# AquaEye_2025-10-07.net
KiCad netlist of a schematic drawn in EasyEDA Pro
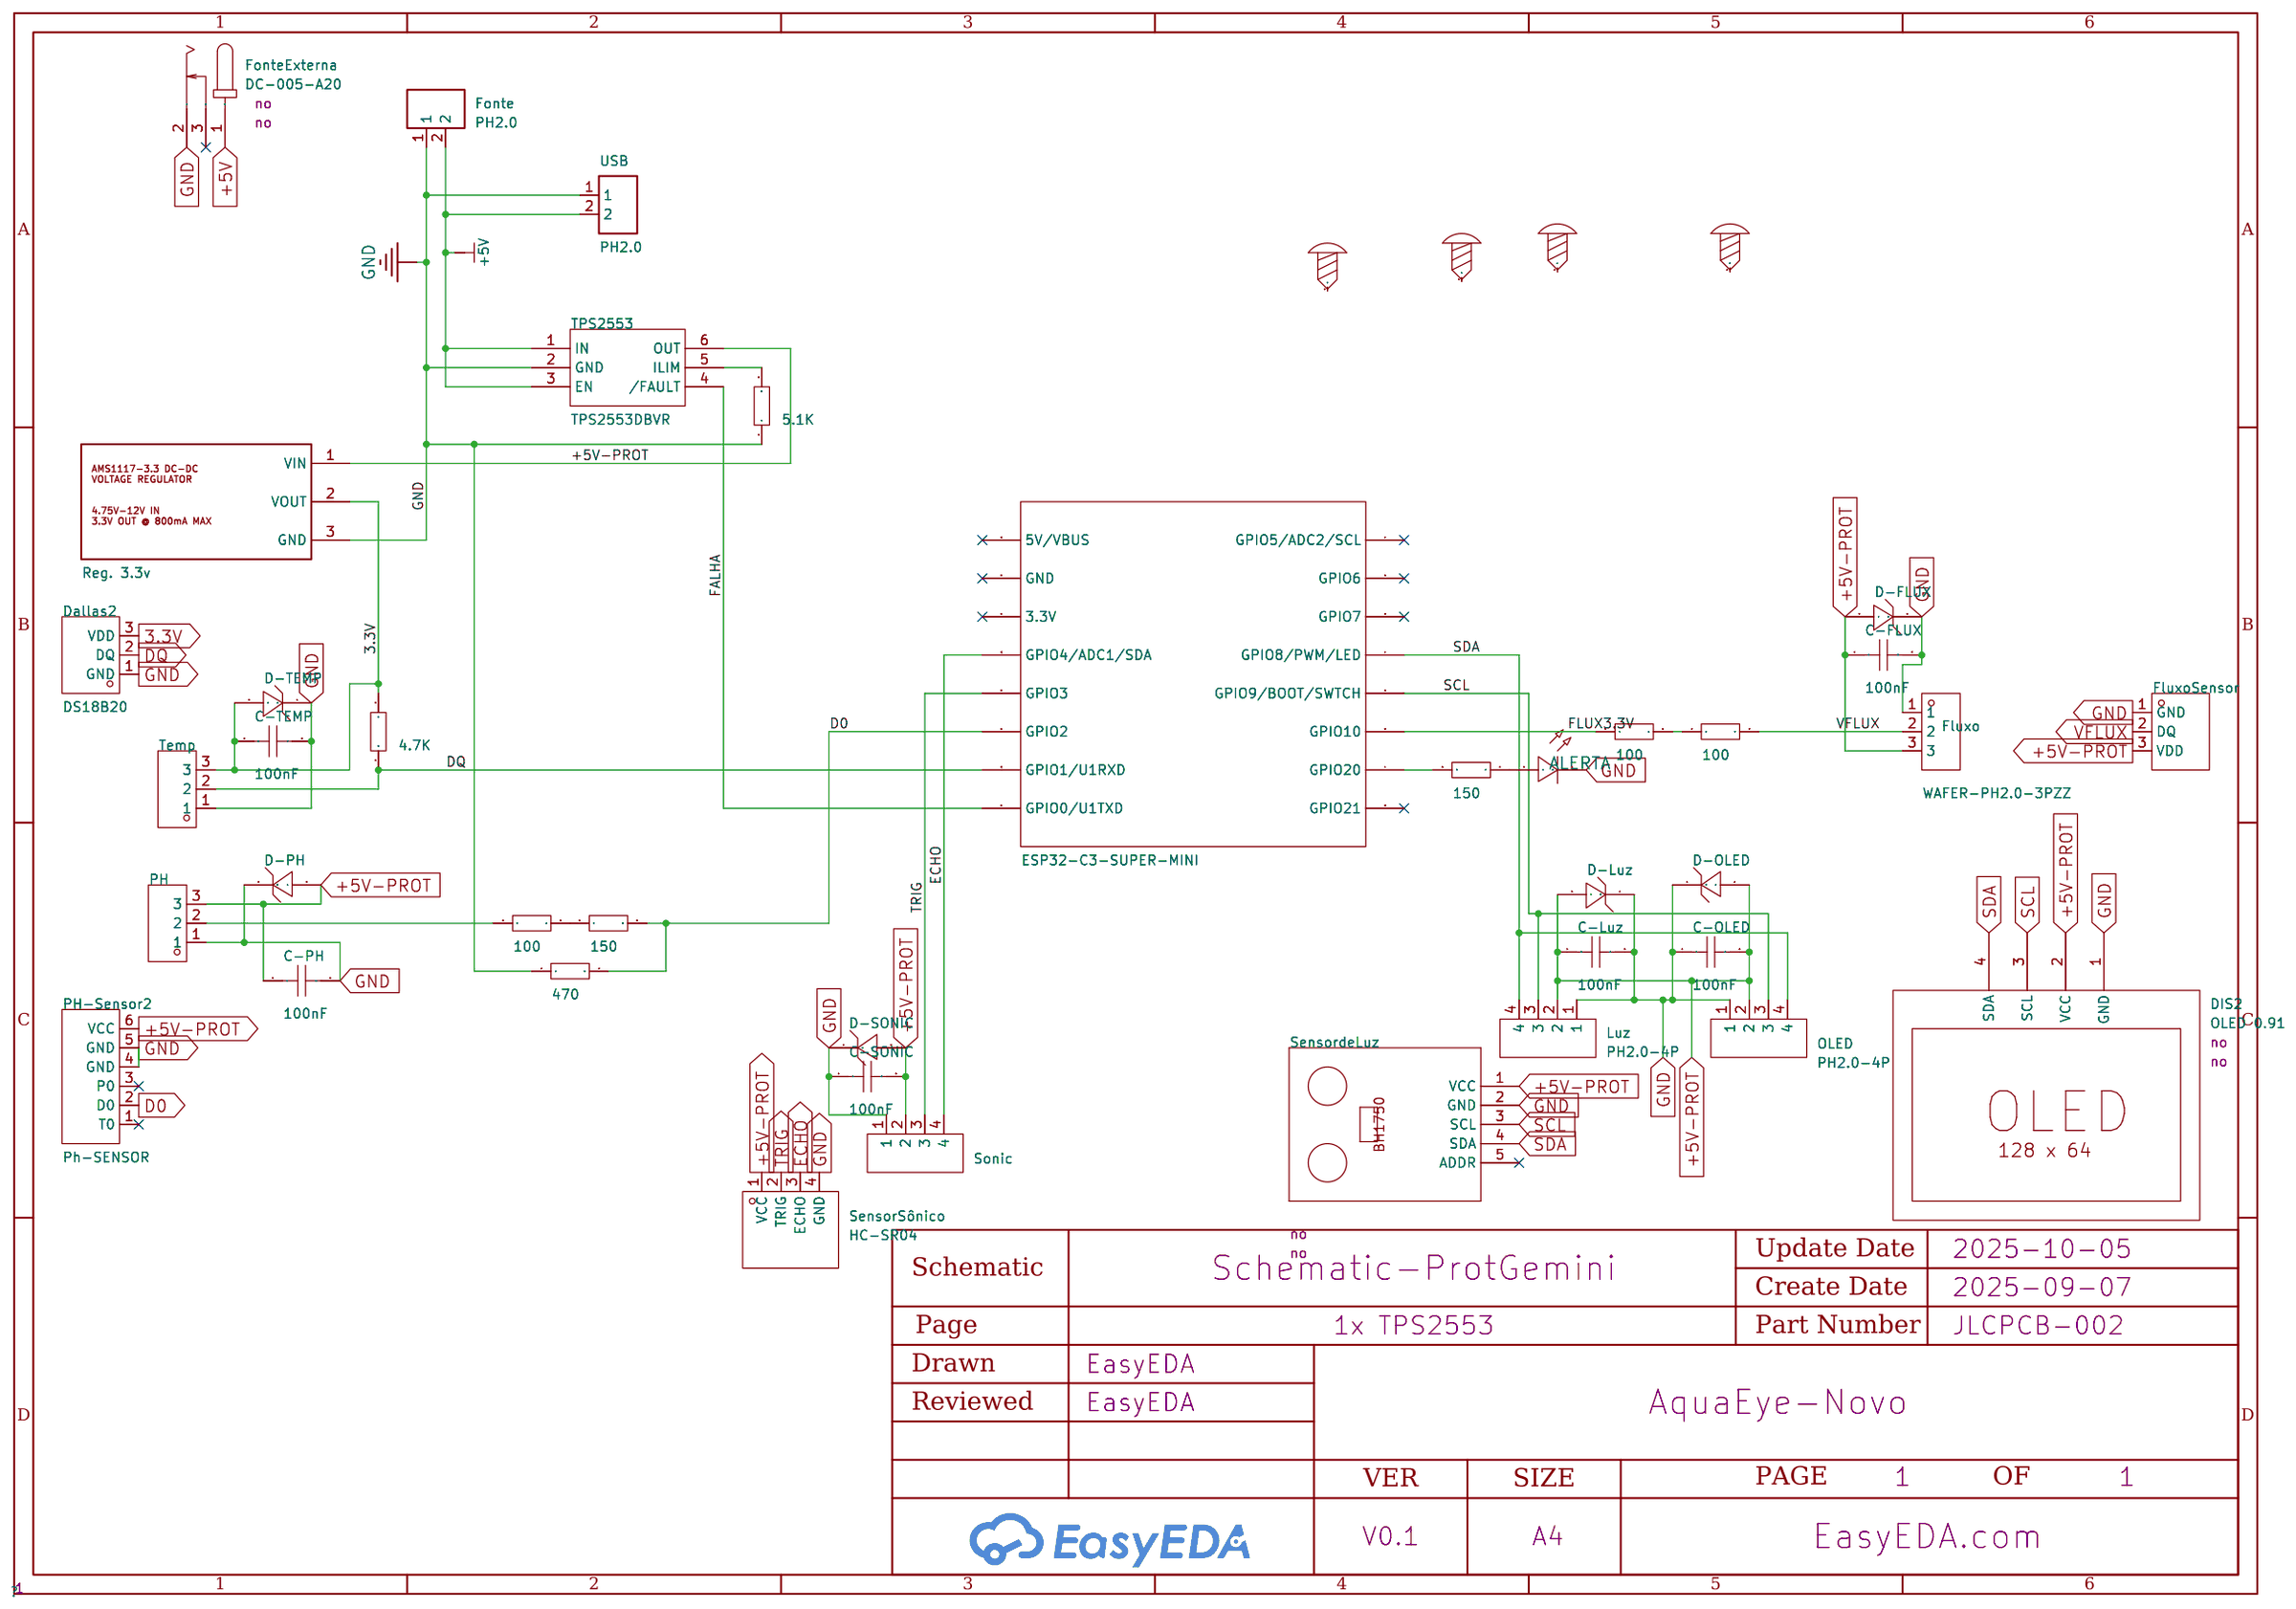
[diagram p0: schematic sheet]

(export (version "E")
  (design (tool "Eeschema 10.0.6"))
  (components
    (comp (ref "ALERTA")
      (value "~")
      (footprint "easyedapro:LED0805-R-RD")
      (libsource (lib "easyedapro") (part "LED_R"))
    )
    (comp (ref "C-FLUX")
      (value "100nF")
      (footprint "easyedapro:CAP-TH_L6.5-W4.0-P5.00-D0.6-S1.20")
      (fields
        (field (name "Manufacturer Part") "DCS104Z26Y5VF6FJ5A0")
        (field (name "Manufacturer") "SHM(南方宏明)")
      )
      (libsource (lib "easyedapro") (part "DCS104Z26Y5VF6FJ5A0"))
    )
    (comp (ref "C-Luz")
      (value "100nF")
      (footprint "easyedapro:CAP-TH_L6.5-W4.0-P5.00-D0.6-S1.20")
      (fields
        (field (name "Manufacturer Part") "DCS104Z26Y5VF6FJ5A0")
        (field (name "Manufacturer") "SHM(南方宏明)")
      )
      (libsource (lib "easyedapro") (part "DCS104Z26Y5VF6FJ5A0"))
    )
    (comp (ref "C-OLED")
      (value "100nF")
      (footprint "easyedapro:CAP-TH_L6.5-W4.0-P5.00-D0.6-S1.20")
      (fields
        (field (name "Manufacturer Part") "DCS104Z26Y5VF6FJ5A0")
        (field (name "Manufacturer") "SHM(南方宏明)")
      )
      (libsource (lib "easyedapro") (part "DCS104Z26Y5VF6FJ5A0"))
    )
    (comp (ref "C-PH")
      (value "100nF")
      (footprint "easyedapro:CAP-TH_L6.5-W4.0-P5.00-D0.6-S1.20")
      (fields
        (field (name "Manufacturer Part") "DCS104Z26Y5VF6FJ5A0")
        (field (name "Manufacturer") "SHM(南方宏明)")
      )
      (libsource (lib "easyedapro") (part "DCS104Z26Y5VF6FJ5A0"))
    )
    (comp (ref "C-SONIC")
      (value "100nF")
      (footprint "easyedapro:CAP-TH_L6.5-W4.0-P5.00-D0.6-S1.20")
      (fields
        (field (name "Manufacturer Part") "DCS104Z26Y5VF6FJ5A0")
        (field (name "Manufacturer") "SHM(南方宏明)")
      )
      (libsource (lib "easyedapro") (part "DCS104Z26Y5VF6FJ5A0"))
    )
    (comp (ref "C-TEMP")
      (value "100nF")
      (footprint "easyedapro:CAP-TH_L6.5-W4.0-P5.00-D0.6-S1.20")
      (fields
        (field (name "Manufacturer Part") "DCS104Z26Y5VF6FJ5A0")
        (field (name "Manufacturer") "SHM(南方宏明)")
      )
      (libsource (lib "easyedapro") (part "DCS104Z26Y5VF6FJ5A0"))
    )
    (comp (ref "D-FLUX")
      (value "SMAJ5.0A")
      (footprint "easyedapro:SMA_L4.3-W2.6-LS5.2-RD")
      (libsource (lib "easyedapro") (part "SMAJ5.0A-C132575"))
    )
    (comp (ref "D-Luz")
      (value "SMAJ5.0A")
      (footprint "easyedapro:SMA_L4.3-W2.6-LS5.2-RD")
      (libsource (lib "easyedapro") (part "SMAJ5.0A-C132575"))
    )
    (comp (ref "D-OLED")
      (value "SMAJ5.0A")
      (footprint "easyedapro:SMA_L4.3-W2.6-LS5.2-RD")
      (libsource (lib "easyedapro") (part "SMAJ5.0A-C132575"))
    )
    (comp (ref "D-PH")
      (value "SMAJ5.0A")
      (footprint "easyedapro:SMA_L4.3-W2.6-LS5.2-RD")
      (libsource (lib "easyedapro") (part "SMAJ5.0A-C132575"))
    )
    (comp (ref "D-SONIC")
      (value "SMAJ5.0A")
      (footprint "easyedapro:SMA_L4.3-W2.6-LS5.2-RD")
      (libsource (lib "easyedapro") (part "SMAJ5.0A-C132575"))
    )
    (comp (ref "D-TEMP")
      (value "SMAJ5.0A")
      (footprint "easyedapro:SMA_L4.3-W2.6-LS5.2-RD")
      (libsource (lib "easyedapro") (part "SMAJ5.0A-C132575"))
    )
    (comp (ref "Dallas2")
      (value "DS18B20")
      (footprint "easyedapro:TO-92-SMD_L4.6-W4.6-P1.27_DS18B20")
      (fields (field (name "Manufacturer") "UMW(友台半导体)"))
      (libsource (lib "easyedapro") (part "DS18B20A10T6"))
    )
    (comp (ref "DIS2")
      (value "OLED 0.91")
      (fields
        (field (name "Manufacturer Part") "SSD1306 I2C OLED")
        (field (name "Add into BOM") "no")
        (field (name "Convert to PCB") "no")
      )
      (libsource (lib "easyedapro") (part "I2C OLED Module (128x64)"))
    )
    (comp (ref "Fluxo")
      (value "WAFER-PH2.0-3PZZ")
      (footprint "easyedapro:CONN-TH_PH2.0D-L-3P")
      (fields (field (name "Manufacturer") "XUNPU(讯普)"))
      (libsource (lib "easyedapro") (part "WAFER-PH2.0-3PZZ"))
    )
    (comp (ref "FluxoSensor")
      (value "DS18B20A10T6")
      (footprint "easyedapro:TO-92-SMD_L4.6-W4.6-P1.27_DS18B20")
      (fields (field (name "Manufacturer") "Mysentech(敏源传感)"))
      (libsource (lib "easyedapro") (part "DS18B20A10T6"))
    )
    (comp (ref "Fonte")
      (value "PH2.0")
      (footprint "easyedapro:CONN-TH_WAFER-PH2.0-2PZZ-Y62")
      (fields
        (field (name "Manufacturer Part") "WAFER-PH2.0-2PZZ-Y62")
        (field (name "Manufacturer") "XUNPU(讯普)")
      )
      (libsource (lib "easyedapro") (part "PH2.0"))
    )
    (comp (ref "FonteExterna")
      (value "DC-005-A20")
      (fields
        (field (name "Manufacturer") "Yuandi(元迪)")
        (field (name "Add into BOM") "no")
        (field (name "Convert to PCB") "no")
      )
      (libsource (lib "easyedapro") (part "DC-005"))
    )
    (comp (ref "Luz")
      (value "PH2.0-4P")
      (footprint "easyedapro:CONN-TH_PH2.0-4P")
      (fields (field (name "Manufacturer") "CAX(创都)"))
      (libsource (lib "easyedapro") (part "PH2.0-4P"))
    )
    (comp (ref "M1")
      (value "Reg. 3.3v")
      (libsource (lib "easyedapro") (part "AMS1117-3.3 DC-DC Voltage Regulator"))
    )
    (comp (ref "OLED")
      (value "PH2.0-4P")
      (footprint "easyedapro:CONN-TH_PH2.0-4P")
      (fields (field (name "Manufacturer") "CAX(创都)"))
      (libsource (lib "easyedapro") (part "PH2.0-4P"))
    )
    (comp (ref "PH")
      (value "WAFER-PH2.0-3PZZ")
      (footprint "easyedapro:CONN-TH_PH2.0D-L-3P")
      (fields (field (name "Manufacturer") "XUNPU(讯普)"))
      (libsource (lib "easyedapro") (part "WAFER-PH2.0-3PZZ"))
    )
    (comp (ref "PH-Sensor2") (value "Ph-SENSOR") (libsource (lib "easyedapro") (part "Ph-SENSOR")))
    (comp (ref "R5") (value "100") (footprint "easyedapro:R0603") (libsource (lib "easyedapro") (part "Res")))
    (comp (ref "R7") (value "100") (footprint "easyedapro:R0603") (libsource (lib "easyedapro") (part "Res")))
    (comp (ref "R8") (value "150") (footprint "easyedapro:R0603") (libsource (lib "easyedapro") (part "Res")))
    (comp (ref "R9") (value "470") (footprint "easyedapro:R0603") (libsource (lib "easyedapro") (part "Res")))
    (comp (ref "R10")
      (value "100")
      (footprint "easyedapro:R0603")
      (libsource (lib "easyedapro") (part "Res"))
    )
    (comp (ref "SCREW1")
      (value "~")
      (footprint "easyedapro:Screw-Hole-M2")
      (libsource (lib "easyedapro") (part "Screw-Hole"))
    )
    (comp (ref "SCREW2")
      (value "~")
      (footprint "easyedapro:Screw-Hole-M2")
      (libsource (lib "easyedapro") (part "Screw-Hole"))
    )
    (comp (ref "SCREW3")
      (value "~")
      (footprint "easyedapro:Screw-Hole-M2")
      (libsource (lib "easyedapro") (part "Screw-Hole"))
    )
    (comp (ref "SCREW4")
      (value "~")
      (footprint "easyedapro:Screw-Hole-M2")
      (libsource (lib "easyedapro") (part "Screw-Hole"))
    )
    (comp (ref "SensordeLuz")
      (value "~")
      (footprint "easyedapro:LIGHT-SENSOR-BH1750")
      (fields (field (name "Add into BOM") "no") (field (name "Convert to PCB") "no"))
      (libsource (lib "easyedapro") (part "LIGHT-SENSOR-BH1750_"))
    )
    (comp (ref "SensorSônico")
      (value "HC-SR04")
      (footprint "easyedapro:TH_HC-SR04V")
      (fields (field (name "Manufacturer") "Universal Microelectronics"))
      (libsource (lib "easyedapro") (part "HC-SR04"))
    )
    (comp (ref "Sonic")
      (value "PH2.0-4P")
      (footprint "easyedapro:CONN-TH_PH2.0-4P")
      (fields (field (name "Manufacturer") "CAX(创都)"))
      (libsource (lib "easyedapro") (part "PH2.0-4P"))
    )
    (comp (ref "Temp")
      (value "WAFER-PH2.0-3PZZ")
      (footprint "easyedapro:CONN-TH_PH2.0D-L-3P")
      (fields (field (name "Manufacturer") "XUNPU(讯普)"))
      (libsource (lib "easyedapro") (part "WAFER-PH2.0-3PZZ"))
    )
    (comp (ref "TPS2553")
      (value "TPS2553DBVR")
      (footprint "easyedapro:SOT-23-6_L2.9-W1.6-P0.95-LS2.8-BR")
      (fields (field (name "Manufacturer") "TI(德州仪器)"))
      (libsource (lib "easyedapro") (part "TPS2553DBVR"))
    )
    (comp (ref "U1")
      (value "4.7K")
      (footprint "easyedapro:R0603")
      (libsource (lib "easyedapro") (part "Res"))
    )
    (comp (ref "U2")
      (value "ESP32-C3-SUPER-MINI")
      (fields (field (name "Manufacturer") "Maker go"))
      (libsource (lib "easyedapro") (part "ESP32-C3-SUPER-MINI"))
    )
    (comp (ref "U3")
      (value "5.1K")
      (footprint "easyedapro:R0603")
      (libsource (lib "easyedapro") (part "Res"))
    )
    (comp (ref "U4") (value "150") (footprint "easyedapro:R0603") (libsource (lib "easyedapro") (part "Res")))
    (comp (ref "USB")
      (value "PH2.0")
      (footprint "easyedapro:CONN-TH_WAFER-PH2.0-2PZZ-Y62")
      (fields
        (field (name "Manufacturer Part") "WAFER-PH2.0-2PZZ-Y62")
        (field (name "Manufacturer") "XUNPU(讯普)")
      )
      (libsource (lib "easyedapro") (part "PH2.0"))
    )
  )
  (nets
    (net (code "1") (name "+5V") (class "Default")
      (node (ref "Fonte") (pin "2") (pinfunction "2_2") (pintype "unspecified"))
      (node (ref "FonteExterna") (pin "1") (pinfunction "1_1") (pintype "unspecified"))
      (node (ref "TPS2553") (pin "1") (pinfunction "IN_1") (pintype "unspecified"))
      (node (ref "TPS2553") (pin "3") (pinfunction "EN_3") (pintype "unspecified"))
      (node (ref "USB") (pin "2") (pinfunction "2_2") (pintype "unspecified"))
    )
    (net (code "2") (name "+5V-PROT") (class "Default")
      (node (ref "C-FLUX") (pin "1") (pinfunction "1_1") (pintype "unspecified"))
      (node (ref "C-Luz") (pin "1") (pinfunction "1_1") (pintype "unspecified"))
      (node (ref "C-OLED") (pin "2") (pinfunction "2_2") (pintype "unspecified"))
      (node (ref "C-PH") (pin "1") (pinfunction "1_1") (pintype "unspecified"))
      (node (ref "C-SONIC") (pin "2") (pinfunction "2_2") (pintype "unspecified"))
      (node (ref "D-FLUX") (pin "2") (pinfunction "A_2") (pintype "unspecified"))
      (node (ref "D-Luz") (pin "2") (pinfunction "A_2") (pintype "unspecified"))
      (node (ref "D-OLED") (pin "2") (pinfunction "A_2") (pintype "unspecified"))
      (node (ref "D-PH") (pin "2") (pinfunction "A_2") (pintype "unspecified"))
      (node (ref "D-SONIC") (pin "2") (pinfunction "A_2") (pintype "unspecified"))
      (node (ref "DIS2") (pin "2") (pinfunction "VCC_2") (pintype "bidirectional"))
      (node (ref "Fluxo") (pin "3") (pinfunction "3_3") (pintype "unspecified"))
      (node (ref "FluxoSensor") (pin "3") (pinfunction "VDD_3") (pintype "unspecified"))
      (node (ref "Luz") (pin "2") (pinfunction "2_2") (pintype "unspecified"))
      (node (ref "M1") (pin "1") (pinfunction "VIN_1") (pintype "unspecified"))
      (node (ref "OLED") (pin "2") (pinfunction "2_2") (pintype "unspecified"))
      (node (ref "PH") (pin "3") (pinfunction "3_3") (pintype "unspecified"))
      (node (ref "PH-Sensor2") (pin "6") (pinfunction "VCC_6") (pintype "input"))
      (node (ref "SensorSônico") (pin "1") (pinfunction "VCC_1") (pintype "unspecified"))
      (node (ref "SensordeLuz") (pin "1") (pinfunction "VCC_1") (pintype "unspecified"))
      (node (ref "Sonic") (pin "2") (pinfunction "2_2") (pintype "unspecified"))
      (node (ref "TPS2553") (pin "6") (pinfunction "OUT_6") (pintype "unspecified"))
    )
    (net (code "3") (name "/FALHA") (class "Default")
      (node (ref "TPS2553") (pin "4") (pinfunction "/FAULT_4") (pintype "unspecified"))
      (node (ref "U2") (pin "9") (pinfunction "GPIO0/U1TXD_9") (pintype "unspecified"))
    )
    (net (code "4") (name "/FLUX3.3V") (class "Default")
      (node (ref "R5") (pin "1") (pinfunction "1_1") (pintype "input"))
      (node (ref "U2") (pin "6") (pinfunction "GPIO10_6") (pintype "unspecified"))
    )
    (net (code "5") (name "3.3V") (class "Default")
      (node (ref "C-TEMP") (pin "1") (pinfunction "1_1") (pintype "unspecified"))
      (node (ref "D-TEMP") (pin "2") (pinfunction "A_2") (pintype "unspecified"))
      (node (ref "Dallas2") (pin "3") (pinfunction "VDD_3") (pintype "unspecified"))
      (node (ref "M1") (pin "2") (pinfunction "VOUT_2") (pintype "unspecified"))
      (node (ref "Temp") (pin "3") (pinfunction "3_3") (pintype "unspecified"))
      (node (ref "U1") (pin "2") (pinfunction "2_2") (pintype "input"))
    )
    (net (code "6") (name "D0") (class "Default")
      (node (ref "PH-Sensor2") (pin "2") (pinfunction "D0_2") (pintype "unspecified"))
      (node (ref "R8") (pin "2") (pinfunction "2_2") (pintype "input"))
      (node (ref "R9") (pin "2") (pinfunction "2_2") (pintype "input"))
      (node (ref "U2") (pin "11") (pinfunction "GPIO2_11") (pintype "unspecified"))
    )
    (net (code "7") (name "DQ") (class "Default")
      (node (ref "Dallas2") (pin "2") (pinfunction "DQ_2") (pintype "unspecified"))
      (node (ref "Temp") (pin "2") (pinfunction "2_2") (pintype "unspecified"))
      (node (ref "U1") (pin "1") (pinfunction "1_1") (pintype "input"))
      (node (ref "U2") (pin "10") (pinfunction "GPIO1/U1RXD_10") (pintype "unspecified"))
    )
    (net (code "8") (name "ECHO") (class "Default")
      (node (ref "SensorSônico") (pin "3") (pinfunction "ECHO_3") (pintype "unspecified"))
      (node (ref "Sonic") (pin "4") (pinfunction "4_4") (pintype "unspecified"))
      (node (ref "U2") (pin "13") (pinfunction "GPIO4/ADC1/SDA_13") (pintype "unspecified"))
    )
    (net (code "9") (name "GND") (class "Default")
      (node (ref "ALERTA") (pin "2") (pinfunction "C_2") (pintype "input"))
      (node (ref "C-FLUX") (pin "2") (pinfunction "2_2") (pintype "unspecified"))
      (node (ref "C-Luz") (pin "2") (pinfunction "2_2") (pintype "unspecified"))
      (node (ref "C-OLED") (pin "1") (pinfunction "1_1") (pintype "unspecified"))
      (node (ref "C-PH") (pin "2") (pinfunction "2_2") (pintype "unspecified"))
      (node (ref "C-SONIC") (pin "1") (pinfunction "1_1") (pintype "unspecified"))
      (node (ref "C-TEMP") (pin "2") (pinfunction "2_2") (pintype "unspecified"))
      (node (ref "D-FLUX") (pin "1") (pinfunction "C_1") (pintype "unspecified"))
      (node (ref "D-Luz") (pin "1") (pinfunction "C_1") (pintype "unspecified"))
      (node (ref "D-OLED") (pin "1") (pinfunction "C_1") (pintype "unspecified"))
      (node (ref "D-PH") (pin "1") (pinfunction "C_1") (pintype "unspecified"))
      (node (ref "D-SONIC") (pin "1") (pinfunction "C_1") (pintype "unspecified"))
      (node (ref "D-TEMP") (pin "1") (pinfunction "C_1") (pintype "unspecified"))
      (node (ref "DIS2") (pin "1") (pinfunction "GND_1") (pintype "bidirectional"))
      (node (ref "Dallas2") (pin "1") (pinfunction "GND_1") (pintype "unspecified"))
      (node (ref "Fluxo") (pin "1") (pinfunction "1_1") (pintype "unspecified"))
      (node (ref "FluxoSensor") (pin "1") (pinfunction "GND_1") (pintype "unspecified"))
      (node (ref "Fonte") (pin "1") (pinfunction "1_1") (pintype "unspecified"))
      (node (ref "FonteExterna") (pin "2") (pinfunction "2_2") (pintype "unspecified"))
      (node (ref "Luz") (pin "1") (pinfunction "1_1") (pintype "unspecified"))
      (node (ref "M1") (pin "3") (pinfunction "GND_3") (pintype "unspecified"))
      (node (ref "OLED") (pin "1") (pinfunction "1_1") (pintype "unspecified"))
      (node (ref "PH") (pin "1") (pinfunction "1_1") (pintype "unspecified"))
      (node (ref "PH-Sensor2") (pin "4") (pinfunction "GND_4") (pintype "input"))
      (node (ref "PH-Sensor2") (pin "5") (pinfunction "GND_5") (pintype "input"))
      (node (ref "R9") (pin "1") (pinfunction "1_1") (pintype "input"))
      (node (ref "SensorSônico") (pin "4") (pinfunction "GND_4") (pintype "unspecified"))
      (node (ref "SensordeLuz") (pin "2") (pinfunction "GND_2") (pintype "unspecified"))
      (node (ref "Sonic") (pin "1") (pinfunction "1_1") (pintype "unspecified"))
      (node (ref "TPS2553") (pin "2") (pinfunction "GND_2") (pintype "unspecified"))
      (node (ref "Temp") (pin "1") (pinfunction "1_1") (pintype "unspecified"))
      (node (ref "U3") (pin "1") (pinfunction "1_1") (pintype "input"))
      (node (ref "USB") (pin "1") (pinfunction "1_1") (pintype "unspecified"))
    )
    (net (code "10") (name "Net-(ALERTA-A)") (class "Default")
      (node (ref "ALERTA") (pin "1") (pinfunction "A_1") (pintype "input"))
      (node (ref "U4") (pin "1") (pinfunction "1_1") (pintype "input"))
    )
    (net (code "11") (name "Net-(PH-Pad2)") (class "Default")
      (node (ref "PH") (pin "2") (pinfunction "2_2") (pintype "unspecified"))
      (node (ref "R7") (pin "1") (pinfunction "1_1") (pintype "input"))
    )
    (net (code "12") (name "Net-(R7-Pad2)") (class "Default")
      (node (ref "R7") (pin "2") (pinfunction "2_2") (pintype "input"))
      (node (ref "R8") (pin "1") (pinfunction "1_1") (pintype "input"))
    )
    (net (code "13") (name "Net-(R10-Pad1)") (class "Default")
      (node (ref "R10") (pin "1") (pinfunction "1_1") (pintype "input"))
      (node (ref "R5") (pin "2") (pinfunction "2_2") (pintype "input"))
    )
    (net (code "14") (name "Net-(TPS2553-ILIM)") (class "Default")
      (node (ref "TPS2553") (pin "5") (pinfunction "ILIM_5") (pintype "unspecified"))
      (node (ref "U3") (pin "2") (pinfunction "2_2") (pintype "input"))
    )
    (net (code "15") (name "Net-(U2-GPIO20)") (class "Default")
      (node (ref "U2") (pin "7") (pinfunction "GPIO20_7") (pintype "unspecified"))
      (node (ref "U4") (pin "2") (pinfunction "2_2") (pintype "input"))
    )
    (net (code "16") (name "SCL") (class "Default")
      (node (ref "DIS2") (pin "3") (pinfunction "SCL_3") (pintype "bidirectional"))
      (node (ref "Luz") (pin "3") (pinfunction "3_3") (pintype "unspecified"))
      (node (ref "OLED") (pin "3") (pinfunction "3_3") (pintype "unspecified"))
      (node (ref "SensordeLuz") (pin "3") (pinfunction "SCL_3") (pintype "bidirectional"))
      (node (ref "U2") (pin "5") (pinfunction "GPIO9/BOOT/SWTCH_5") (pintype "unspecified"))
    )
    (net (code "17") (name "SDA") (class "Default")
      (node (ref "DIS2") (pin "4") (pinfunction "SDA_4") (pintype "bidirectional"))
      (node (ref "Luz") (pin "4") (pinfunction "4_4") (pintype "unspecified"))
      (node (ref "OLED") (pin "4") (pinfunction "4_4") (pintype "unspecified"))
      (node (ref "SensordeLuz") (pin "4") (pinfunction "SDA_4") (pintype "bidirectional"))
      (node (ref "U2") (pin "4") (pinfunction "GPIO8/PWM/LED_4") (pintype "unspecified"))
    )
    (net (code "18") (name "TRIG") (class "Default")
      (node (ref "SensorSônico") (pin "2") (pinfunction "TRIG_2") (pintype "unspecified"))
      (node (ref "Sonic") (pin "3") (pinfunction "3_3") (pintype "unspecified"))
      (node (ref "U2") (pin "12") (pinfunction "GPIO3_12") (pintype "unspecified"))
    )
    (net (code "19") (name "VFLUX") (class "Default")
      (node (ref "Fluxo") (pin "2") (pinfunction "2_2") (pintype "unspecified"))
      (node (ref "FluxoSensor") (pin "2") (pinfunction "DQ_2") (pintype "unspecified"))
      (node (ref "R10") (pin "2") (pinfunction "2_2") (pintype "input"))
    )
    (net (code "20") (name "unconnected-(FonteExterna-Pad3)") (class "Default")
      (node (ref "FonteExterna") (pin "3") (pinfunction "3_3") (pintype "unspecified+no_connect"))
    )
    (net (code "21") (name "unconnected-(PH-Sensor2-P0-Pad3)") (class "Default")
      (node (ref "PH-Sensor2") (pin "3") (pinfunction "P0_3") (pintype "unspecified+no_connect"))
    )
    (net (code "22") (name "unconnected-(PH-Sensor2-T0-Pad1)") (class "Default")
      (node (ref "PH-Sensor2") (pin "1") (pinfunction "T0_1") (pintype "unspecified+no_connect"))
    )
    (net (code "23") (name "unconnected-(SCREW1-Pad1)") (class "Default")
      (node (ref "SCREW1") (pin "1") (pinfunction "1_1") (pintype "input"))
    )
    (net (code "24") (name "unconnected-(SCREW2-Pad1)") (class "Default")
      (node (ref "SCREW2") (pin "1") (pinfunction "1_1") (pintype "input"))
    )
    (net (code "25") (name "unconnected-(SCREW3-Pad1)") (class "Default")
      (node (ref "SCREW3") (pin "1") (pinfunction "1_1") (pintype "input"))
    )
    (net (code "26") (name "unconnected-(SCREW4-Pad1)") (class "Default")
      (node (ref "SCREW4") (pin "1") (pinfunction "1_1") (pintype "input"))
    )
    (net (code "27") (name "unconnected-(SensordeLuz-ADDR-Pad5)") (class "Default")
      (node (ref "SensordeLuz") (pin "5") (pinfunction "ADDR_5") (pintype "bidirectional+no_connect"))
    )
    (net (code "28") (name "unconnected-(U2-3.3V-Pad14)") (class "Default")
      (node (ref "U2") (pin "14") (pinfunction "3.3V_14") (pintype "unspecified+no_connect"))
    )
    (net (code "29") (name "unconnected-(U2-5V{slash}VBUS-Pad16)") (class "Default")
      (node (ref "U2") (pin "16") (pinfunction "5V/VBUS_16") (pintype "unspecified+no_connect"))
    )
    (net (code "30") (name "unconnected-(U2-GND-Pad15)") (class "Default")
      (node (ref "U2") (pin "15") (pinfunction "GND_15") (pintype "unspecified+no_connect"))
    )
    (net (code "31") (name "unconnected-(U2-GPIO5{slash}ADC2{slash}SCL-Pad1)") (class "Default")
      (node (ref "U2") (pin "1") (pinfunction "GPIO5/ADC2/SCL_1") (pintype "unspecified+no_connect"))
    )
    (net (code "32") (name "unconnected-(U2-GPIO6-Pad2)") (class "Default")
      (node (ref "U2") (pin "2") (pinfunction "GPIO6_2") (pintype "unspecified+no_connect"))
    )
    (net (code "33") (name "unconnected-(U2-GPIO7-Pad3)") (class "Default")
      (node (ref "U2") (pin "3") (pinfunction "GPIO7_3") (pintype "unspecified+no_connect"))
    )
    (net (code "34") (name "unconnected-(U2-GPIO21-Pad8)") (class "Default")
      (node (ref "U2") (pin "8") (pinfunction "GPIO21_8") (pintype "unspecified+no_connect"))
    )
  )
)
